# board_A500_A1000.net
KiCad netlist of a schematic drawn in EAGLE
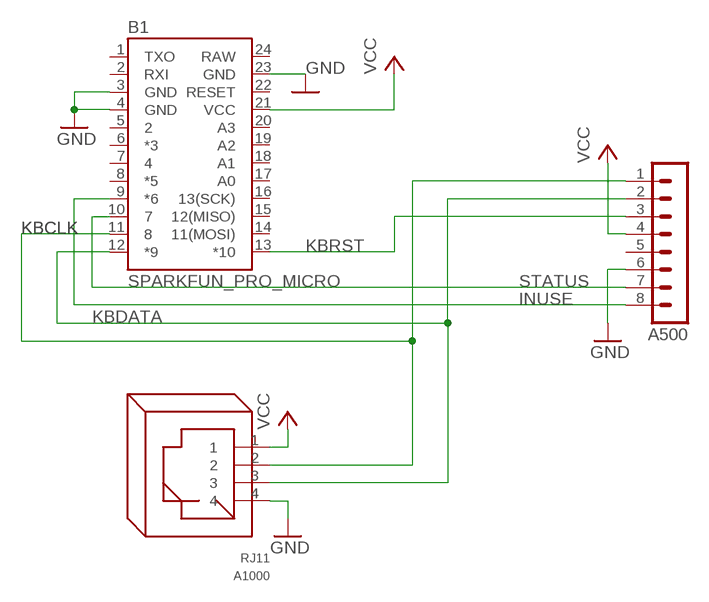
[diagram p0: schematic, sheet 1]

(export (version "E")
  (design (tool "Eeschema 10.0.6"))
  (components
    (comp (ref "A500")
      (value "MA08-1")
      (footprint "eagle-import:MA08-1")
      (libsource (lib "eagle-import") (part "MA08-1"))
    )
    (comp (ref "A1000")
      (value "RJ11")
      (footprint "eagle-import:RJ11")
      (libsource (lib "eagle-import") (part "RJ11"))
    )
    (comp (ref "B1")
      (value "SPARKFUN_PRO_MICRO")
      (footprint "eagle-import:SPARKFUN_PRO_MICRO")
      (libsource (lib "eagle-import") (part "SPARKFUN_PRO_MICRO"))
    )
  )
  (nets
    (net (code "1") (name "/INUSE") (class "Default")
      (node (ref "A500") (pin "8") (pinfunction "8_8") (pintype "passive"))
      (node (ref "B1") (pin "9") (pinfunction "*6_9") (pintype "bidirectional"))
    )
    (net (code "2") (name "/KBCLK") (class "Default")
      (node (ref "A1000") (pin "2") (pinfunction "2_2") (pintype "bidirectional"))
      (node (ref "A500") (pin "1") (pinfunction "1_1") (pintype "passive"))
      (node (ref "B1") (pin "11") (pinfunction "8_11") (pintype "bidirectional"))
    )
    (net (code "3") (name "/KBDATA") (class "Default")
      (node (ref "A1000") (pin "3") (pinfunction "3_3") (pintype "bidirectional"))
      (node (ref "A500") (pin "2") (pinfunction "2_2") (pintype "passive"))
      (node (ref "B1") (pin "12") (pinfunction "*9_12") (pintype "bidirectional"))
    )
    (net (code "4") (name "/KBRST") (class "Default")
      (node (ref "A500") (pin "3") (pinfunction "3_3") (pintype "passive"))
      (node (ref "B1") (pin "13") (pinfunction "*10_13") (pintype "bidirectional"))
    )
    (net (code "5") (name "/RAW") (class "Default")
      (node (ref "B1") (pin "24") (pinfunction "RAW_24") (pintype "power_in"))
    )
    (net (code "6") (name "/STATUS") (class "Default")
      (node (ref "A500") (pin "7") (pinfunction "7_7") (pintype "passive"))
      (node (ref "B1") (pin "10") (pinfunction "7_10") (pintype "bidirectional"))
    )
    (net (code "7") (name "GND") (class "Default")
      (node (ref "A1000") (pin "4") (pinfunction "4_4") (pintype "bidirectional"))
      (node (ref "A500") (pin "6") (pinfunction "6_6") (pintype "passive"))
      (node (ref "B1") (pin "23") (pinfunction "GND_23") (pintype "power_in"))
      (node (ref "B1") (pin "3") (pinfunction "GND_3") (pintype "power_in"))
      (node (ref "B1") (pin "4") (pinfunction "GND_4") (pintype "power_in"))
    )
    (net (code "8") (name "VCC") (class "Default")
      (node (ref "A1000") (pin "1") (pinfunction "1_1") (pintype "bidirectional"))
      (node (ref "A500") (pin "4") (pinfunction "4_4") (pintype "passive"))
      (node (ref "B1") (pin "21") (pinfunction "VCC_21") (pintype "power_in"))
    )
    (net (code "9") (name "unconnected-(A500-Pad5)") (class "Default")
      (node (ref "A500") (pin "5") (pinfunction "5_5") (pintype "passive"))
    )
    (net (code "10") (name "unconnected-(B1-*3-Pad6)") (class "Default")
      (node (ref "B1") (pin "6") (pinfunction "*3_6") (pintype "bidirectional"))
    )
    (net (code "11") (name "unconnected-(B1-*5-Pad8)") (class "Default")
      (node (ref "B1") (pin "8") (pinfunction "*5_8") (pintype "bidirectional"))
    )
    (net (code "12") (name "unconnected-(B1-2-Pad5)") (class "Default")
      (node (ref "B1") (pin "5") (pinfunction "2_5") (pintype "bidirectional"))
    )
    (net (code "13") (name "unconnected-(B1-4-Pad7)") (class "Default")
      (node (ref "B1") (pin "7") (pinfunction "4_7") (pintype "bidirectional"))
    )
    (net (code "14") (name "unconnected-(B1-11(MOSI)-Pad14)") (class "Default")
      (node (ref "B1") (pin "14") (pinfunction "11(MOSI)_14") (pintype "bidirectional"))
    )
    (net (code "15") (name "unconnected-(B1-12(MISO)-Pad15)") (class "Default")
      (node (ref "B1") (pin "15") (pinfunction "12(MISO)_15") (pintype "bidirectional"))
    )
    (net (code "16") (name "unconnected-(B1-13(SCK)-Pad16)") (class "Default")
      (node (ref "B1") (pin "16") (pinfunction "13(SCK)_16") (pintype "bidirectional"))
    )
    (net (code "17") (name "unconnected-(B1-A0-Pad17)") (class "Default")
      (node (ref "B1") (pin "17") (pinfunction "A0_17") (pintype "bidirectional"))
    )
    (net (code "18") (name "unconnected-(B1-A1-Pad18)") (class "Default")
      (node (ref "B1") (pin "18") (pinfunction "A1_18") (pintype "bidirectional"))
    )
    (net (code "19") (name "unconnected-(B1-A2-Pad19)") (class "Default")
      (node (ref "B1") (pin "19") (pinfunction "A2_19") (pintype "bidirectional"))
    )
    (net (code "20") (name "unconnected-(B1-A3-Pad20)") (class "Default")
      (node (ref "B1") (pin "20") (pinfunction "A3_20") (pintype "bidirectional"))
    )
    (net (code "21") (name "unconnected-(B1-RESET-Pad22)") (class "Default")
      (node (ref "B1") (pin "22") (pinfunction "RESET_22") (pintype "bidirectional"))
    )
    (net (code "22") (name "unconnected-(B1-RXI-Pad2)") (class "Default")
      (node (ref "B1") (pin "2") (pinfunction "RXI_2") (pintype "bidirectional"))
    )
    (net (code "23") (name "unconnected-(B1-TXO-Pad1)") (class "Default")
      (node (ref "B1") (pin "1") (pinfunction "TXO_1") (pintype "bidirectional"))
    )
  )
)
